# main_board.net
KiCad netlist of a schematic drawn in Altium Designer
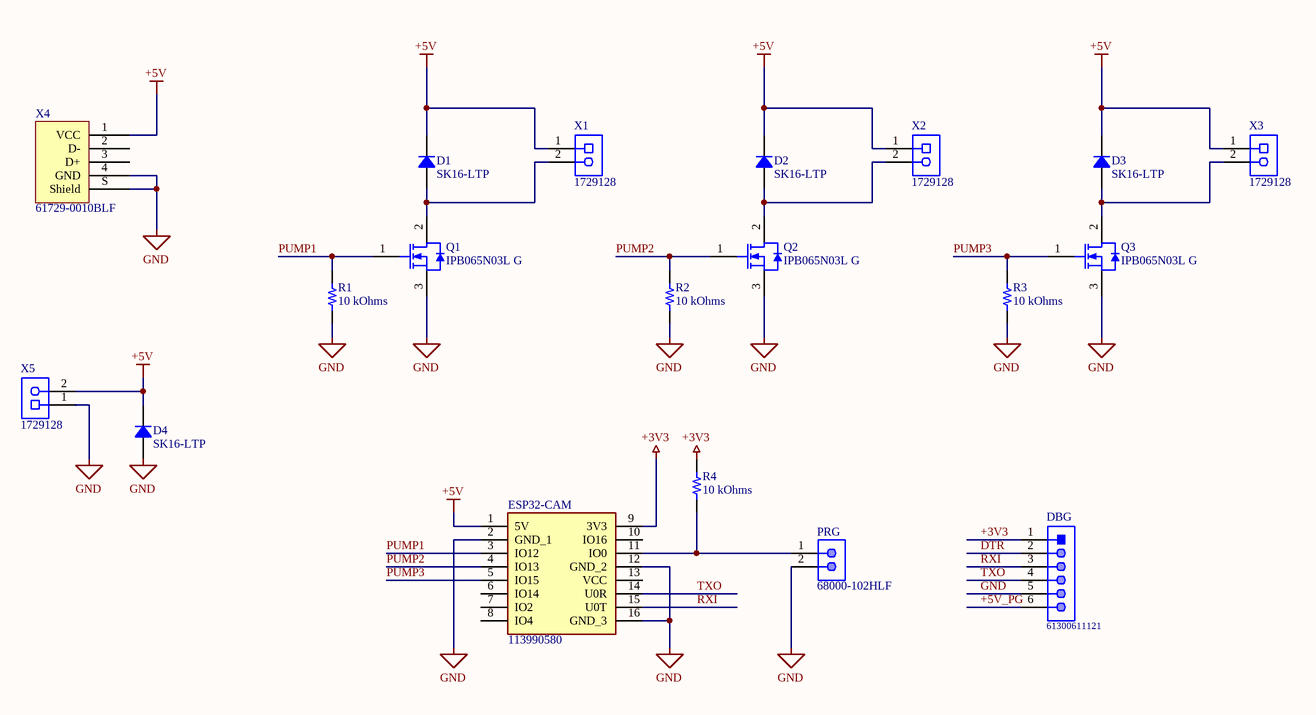
[diagram p0: main_board.SchDoc]

(export (version "E")
  (design (tool "Eeschema 10.0.6"))
  (components
    (comp (ref "D1")
      (value "SK16-LTP")
      (footprint "DO214AA SMB")
      (description "DIODE SCHOTTKY 60V 1A DO214AA")
      (fields (field (name "MANUFACTURER") "Micro Commercial Co"))
      (libsource (lib "CL") (part "Diode"))
    )
    (comp (ref "D2")
      (value "SK16-LTP")
      (footprint "DO214AA SMB")
      (description "DIODE SCHOTTKY 60V 1A DO214AA")
      (fields (field (name "MANUFACTURER") "Micro Commercial Co"))
      (libsource (lib "CL") (part "Diode"))
    )
    (comp (ref "D3")
      (value "SK16-LTP")
      (footprint "DO214AA SMB")
      (description "DIODE SCHOTTKY 60V 1A DO214AA")
      (fields (field (name "MANUFACTURER") "Micro Commercial Co"))
      (libsource (lib "CL") (part "Diode"))
    )
    (comp (ref "D4")
      (value "SK16-LTP")
      (footprint "DO214AA SMB")
      (description "DIODE SCHOTTKY 60V 1A DO214AA")
      (fields (field (name "MANUFACTURER") "Micro Commercial Co"))
      (libsource (lib "CL") (part "Diode"))
    )
    (comp (ref "DBG")
      (value "61300611121")
      (footprint "61300611121")
      (description "THT Vertical Pin Header WR-PHD, Pitch 2.54 mm, Single Row, 6 pins")
      (fields (field (name "MANUFACTURER") "Wurth Elektronik") (field (name "PUBLISHER") "WurthElektronik"))
      (libsource (lib "Altium Content Vault") (part "WE-CN-1P-M-R6"))
    )
    (comp (ref "ESP32-CAM")
      (value "113990580")
      (footprint "SamacSys:113990580")
      (description "Integrated Circuit")
      (fields (field (name "MOUSER PART NUMBER") "713-113990580"))
      (libsource (lib "*") (part "113990580"))
    )
    (comp (ref "PRG")
      (value "68000-102HLF")
      (footprint "AMPH-68000-102HLF_V")
      (description "Male Header, Pitch 2.54 mm, 1 x 2 Position, Height 8.38 mm, Tail Length 2.41 mm, RoHS, Bulk")
      (fields (field (name "MANUFACTURER") "FCI"))
      (libsource (lib "Altium Content Vault") (part "CN-1P-M-R2"))
    )
    (comp (ref "Q1")
      (value "IPB065N03L G")
      (footprint "INF-PG-TO-263-3-2_A_L")
      (fields (field (name "MANUFACTURER") "Infineon"))
      (libsource (lib "Altium Content Vault") (part "INF-NEMOS-GDS-3"))
    )
    (comp (ref "Q2")
      (value "IPB065N03L G")
      (footprint "INF-PG-TO-263-3-2_A_L")
      (fields (field (name "MANUFACTURER") "Infineon"))
      (libsource (lib "Altium Content Vault") (part "INF-NEMOS-GDS-3"))
    )
    (comp (ref "Q3")
      (value "IPB065N03L G")
      (footprint "INF-PG-TO-263-3-2_A_L")
      (fields (field (name "MANUFACTURER") "Infineon"))
      (libsource (lib "Altium Content Vault") (part "INF-NEMOS-GDS-3"))
    )
    (comp (ref "R1")
      (value "10 kOhms")
      (footprint "RES 1206_3216")
      (description "RES SMD 10K OHM 1% 1/4W 1206")
      (fields
        (field (name "PART NUMBER") "CRG1206F10K")
        (field (name "MANUFACTURER") "TE Connectivity Passive Product")
      )
      (libsource (lib "CL") (part "Resistor"))
    )
    (comp (ref "R2")
      (value "10 kOhms")
      (footprint "RES 1206_3216")
      (description "RES SMD 10K OHM 1% 1/4W 1206")
      (fields
        (field (name "PART NUMBER") "CRG1206F10K")
        (field (name "MANUFACTURER") "TE Connectivity Passive Product")
      )
      (libsource (lib "CL") (part "Resistor"))
    )
    (comp (ref "R3")
      (value "10 kOhms")
      (footprint "RES 1206_3216")
      (description "RES SMD 10K OHM 1% 1/4W 1206")
      (fields
        (field (name "PART NUMBER") "CRG1206F10K")
        (field (name "MANUFACTURER") "TE Connectivity Passive Product")
      )
      (libsource (lib "CL") (part "Resistor"))
    )
    (comp (ref "R4")
      (value "10 kOhms")
      (footprint "RES 1206_3216")
      (description "RES SMD 10K OHM 1% 1/4W 1206")
      (fields
        (field (name "PART NUMBER") "CRG1206F10K")
        (field (name "MANUFACTURER") "TE Connectivity Passive Product")
      )
      (libsource (lib "CL") (part "Resistor"))
    )
    (comp (ref "X1")
      (value "1729128")
      (footprint "PHOE-1729128-2_V")
      (description "PCB Terminal Block, 13.5 A, 400 V, 2-Pin THD, RoHS, Bulk")
      (fields (field (name "MANUFACTURER") "Phoenix Contact"))
      (libsource (lib "Altium Content Vault") (part "CN-2P-F-R2"))
    )
    (comp (ref "X2")
      (value "1729128")
      (footprint "PHOE-1729128-2_V")
      (description "PCB Terminal Block, 13.5 A, 400 V, 2-Pin THD, RoHS, Bulk")
      (fields (field (name "MANUFACTURER") "Phoenix Contact"))
      (libsource (lib "Altium Content Vault") (part "CN-2P-F-R2"))
    )
    (comp (ref "X3")
      (value "1729128")
      (footprint "PHOE-1729128-2_V")
      (description "PCB Terminal Block, 13.5 A, 400 V, 2-Pin THD, RoHS, Bulk")
      (fields (field (name "MANUFACTURER") "Phoenix Contact"))
      (libsource (lib "Altium Content Vault") (part "CN-2P-F-R2"))
    )
    (comp (ref "X4")
      (value "61729-0010BLF")
      (footprint "FCI USB 61729-0010BLF")
      (description "CONN RCPT USB2.0 TYPEB 4POS R/A")
      (fields (field (name "MANUFACTURER") "Amphenol ICC (FCI)"))
      (libsource (lib "CL") (part "USB 2.0 Type B"))
    )
    (comp (ref "X5")
      (value "1729128")
      (footprint "PHOE-1729128-2_V")
      (description "PCB Terminal Block, 13.5 A, 400 V, 2-Pin THD, RoHS, Bulk")
      (fields (field (name "MANUFACTURER") "Phoenix Contact"))
      (libsource (lib "") (part "CN-2P-F-R2_1"))
    )
  )
  (nets
    (net (code "1") (name "+3V3") (class "Default")
      (node (ref "DBG") (pin "1") (pinfunction "1_1") (pintype "passive"))
      (node (ref "ESP32-CAM") (pin "9") (pinfunction "3V3_9") (pintype "passive"))
      (node (ref "R4") (pin "1") (pinfunction "1_1") (pintype "passive"))
    )
    (net (code "2") (name "+5V") (class "Default")
      (node (ref "D1") (pin "2") (pinfunction "2_2") (pintype "passive"))
      (node (ref "D2") (pin "2") (pinfunction "2_2") (pintype "passive"))
      (node (ref "D3") (pin "2") (pinfunction "2_2") (pintype "passive"))
      (node (ref "D4") (pin "2") (pinfunction "2_2") (pintype "passive"))
      (node (ref "ESP32-CAM") (pin "1") (pinfunction "5V_1") (pintype "passive"))
      (node (ref "X1") (pin "1") (pinfunction "1_1") (pintype "passive"))
      (node (ref "X2") (pin "1") (pinfunction "1_1") (pintype "passive"))
      (node (ref "X3") (pin "1") (pinfunction "1_1") (pintype "passive"))
      (node (ref "X4") (pin "1") (pinfunction "VCC_1") (pintype "passive"))
      (node (ref "X5") (pin "2") (pinfunction "2_2") (pintype "passive"))
    )
    (net (code "3") (name "/+5V_PG") (class "Default")
      (node (ref "DBG") (pin "6") (pinfunction "6_6") (pintype "passive"))
    )
    (net (code "4") (name "/DTR") (class "Default")
      (node (ref "DBG") (pin "2") (pinfunction "2_2") (pintype "passive"))
    )
    (net (code "5") (name "/PUMP1") (class "Default")
      (node (ref "ESP32-CAM") (pin "3") (pinfunction "IO12_3") (pintype "passive"))
      (node (ref "Q1") (pin "1") (pinfunction "GATE_1") (pintype "passive"))
      (node (ref "R1") (pin "1") (pinfunction "1_1") (pintype "passive"))
    )
    (net (code "6") (name "/PUMP2") (class "Default")
      (node (ref "ESP32-CAM") (pin "4") (pinfunction "IO13_4") (pintype "passive"))
      (node (ref "Q2") (pin "1") (pinfunction "GATE_1") (pintype "passive"))
      (node (ref "R2") (pin "1") (pinfunction "1_1") (pintype "passive"))
    )
    (net (code "7") (name "/PUMP3") (class "Default")
      (node (ref "ESP32-CAM") (pin "5") (pinfunction "IO15_5") (pintype "passive"))
      (node (ref "Q3") (pin "1") (pinfunction "GATE_1") (pintype "passive"))
      (node (ref "R3") (pin "1") (pinfunction "1_1") (pintype "passive"))
    )
    (net (code "8") (name "/RXI") (class "Default")
      (node (ref "DBG") (pin "3") (pinfunction "3_3") (pintype "passive"))
      (node (ref "ESP32-CAM") (pin "15") (pinfunction "U0T_15") (pintype "passive"))
    )
    (net (code "9") (name "/TXO") (class "Default")
      (node (ref "DBG") (pin "4") (pinfunction "4_4") (pintype "passive"))
      (node (ref "ESP32-CAM") (pin "14") (pinfunction "U0R_14") (pintype "passive"))
    )
    (net (code "10") (name "GND") (class "Default")
      (node (ref "D4") (pin "1") (pinfunction "1_1") (pintype "passive"))
      (node (ref "DBG") (pin "5") (pinfunction "5_5") (pintype "passive"))
      (node (ref "ESP32-CAM") (pin "12") (pinfunction "GND_2_12") (pintype "passive"))
      (node (ref "ESP32-CAM") (pin "16") (pinfunction "GND_3_16") (pintype "passive"))
      (node (ref "ESP32-CAM") (pin "2") (pinfunction "GND_1_2") (pintype "passive"))
      (node (ref "PRG") (pin "2") (pinfunction "2_2") (pintype "passive"))
      (node (ref "Q1") (pin "3") (pinfunction "SOURCE_3") (pintype "passive"))
      (node (ref "Q2") (pin "3") (pinfunction "SOURCE_3") (pintype "passive"))
      (node (ref "Q3") (pin "3") (pinfunction "SOURCE_3") (pintype "passive"))
      (node (ref "R1") (pin "2") (pinfunction "2_2") (pintype "passive"))
      (node (ref "R2") (pin "2") (pinfunction "2_2") (pintype "passive"))
      (node (ref "R3") (pin "2") (pinfunction "2_2") (pintype "passive"))
      (node (ref "X4") (pin "4") (pinfunction "GND_4") (pintype "passive"))
      (node (ref "X4") (pin "S") (pinfunction "Shield_S") (pintype "passive"))
      (node (ref "X5") (pin "1") (pinfunction "1_1") (pintype "passive"))
    )
    (net (code "11") (name "Net-(ESP32-CAM-IO0)") (class "Default")
      (node (ref "ESP32-CAM") (pin "11") (pinfunction "IO0_11") (pintype "passive"))
      (node (ref "PRG") (pin "1") (pinfunction "1_1") (pintype "passive"))
      (node (ref "R4") (pin "2") (pinfunction "2_2") (pintype "passive"))
    )
    (net (code "12") (name "Net-(Q1-DRAIN)") (class "Default")
      (node (ref "D1") (pin "1") (pinfunction "1_1") (pintype "passive"))
      (node (ref "Q1") (pin "2") (pinfunction "DRAIN_2") (pintype "passive"))
      (node (ref "X1") (pin "2") (pinfunction "2_2") (pintype "passive"))
    )
    (net (code "13") (name "Net-(Q2-DRAIN)") (class "Default")
      (node (ref "D2") (pin "1") (pinfunction "1_1") (pintype "passive"))
      (node (ref "Q2") (pin "2") (pinfunction "DRAIN_2") (pintype "passive"))
      (node (ref "X2") (pin "2") (pinfunction "2_2") (pintype "passive"))
    )
    (net (code "14") (name "Net-(Q3-DRAIN)") (class "Default")
      (node (ref "D3") (pin "1") (pinfunction "1_1") (pintype "passive"))
      (node (ref "Q3") (pin "2") (pinfunction "DRAIN_2") (pintype "passive"))
      (node (ref "X3") (pin "2") (pinfunction "2_2") (pintype "passive"))
    )
    (net (code "15") (name "unconnected-(ESP32-CAM-IO2-Pad7)") (class "Default")
      (node (ref "ESP32-CAM") (pin "7") (pinfunction "IO2_7") (pintype "passive"))
    )
    (net (code "16") (name "unconnected-(ESP32-CAM-IO4-Pad8)") (class "Default")
      (node (ref "ESP32-CAM") (pin "8") (pinfunction "IO4_8") (pintype "passive"))
    )
    (net (code "17") (name "unconnected-(ESP32-CAM-IO14-Pad6)") (class "Default")
      (node (ref "ESP32-CAM") (pin "6") (pinfunction "IO14_6") (pintype "passive"))
    )
    (net (code "18") (name "unconnected-(ESP32-CAM-IO16-Pad10)") (class "Default")
      (node (ref "ESP32-CAM") (pin "10") (pinfunction "IO16_10") (pintype "passive"))
    )
    (net (code "19") (name "unconnected-(ESP32-CAM-VCC-Pad13)") (class "Default")
      (node (ref "ESP32-CAM") (pin "13") (pinfunction "VCC_13") (pintype "passive"))
    )
    (net (code "20") (name "unconnected-(X4-D+-Pad3)") (class "Default")
      (node (ref "X4") (pin "3") (pinfunction "D+_3") (pintype "passive"))
    )
    (net (code "21") (name "unconnected-(X4-D--Pad2)") (class "Default")
      (node (ref "X4") (pin "2") (pinfunction "D-_2") (pintype "passive"))
    )
  )
)
